# DS157-1_2-C.net
KiCad netlist of a schematic drawn in Altium Designer
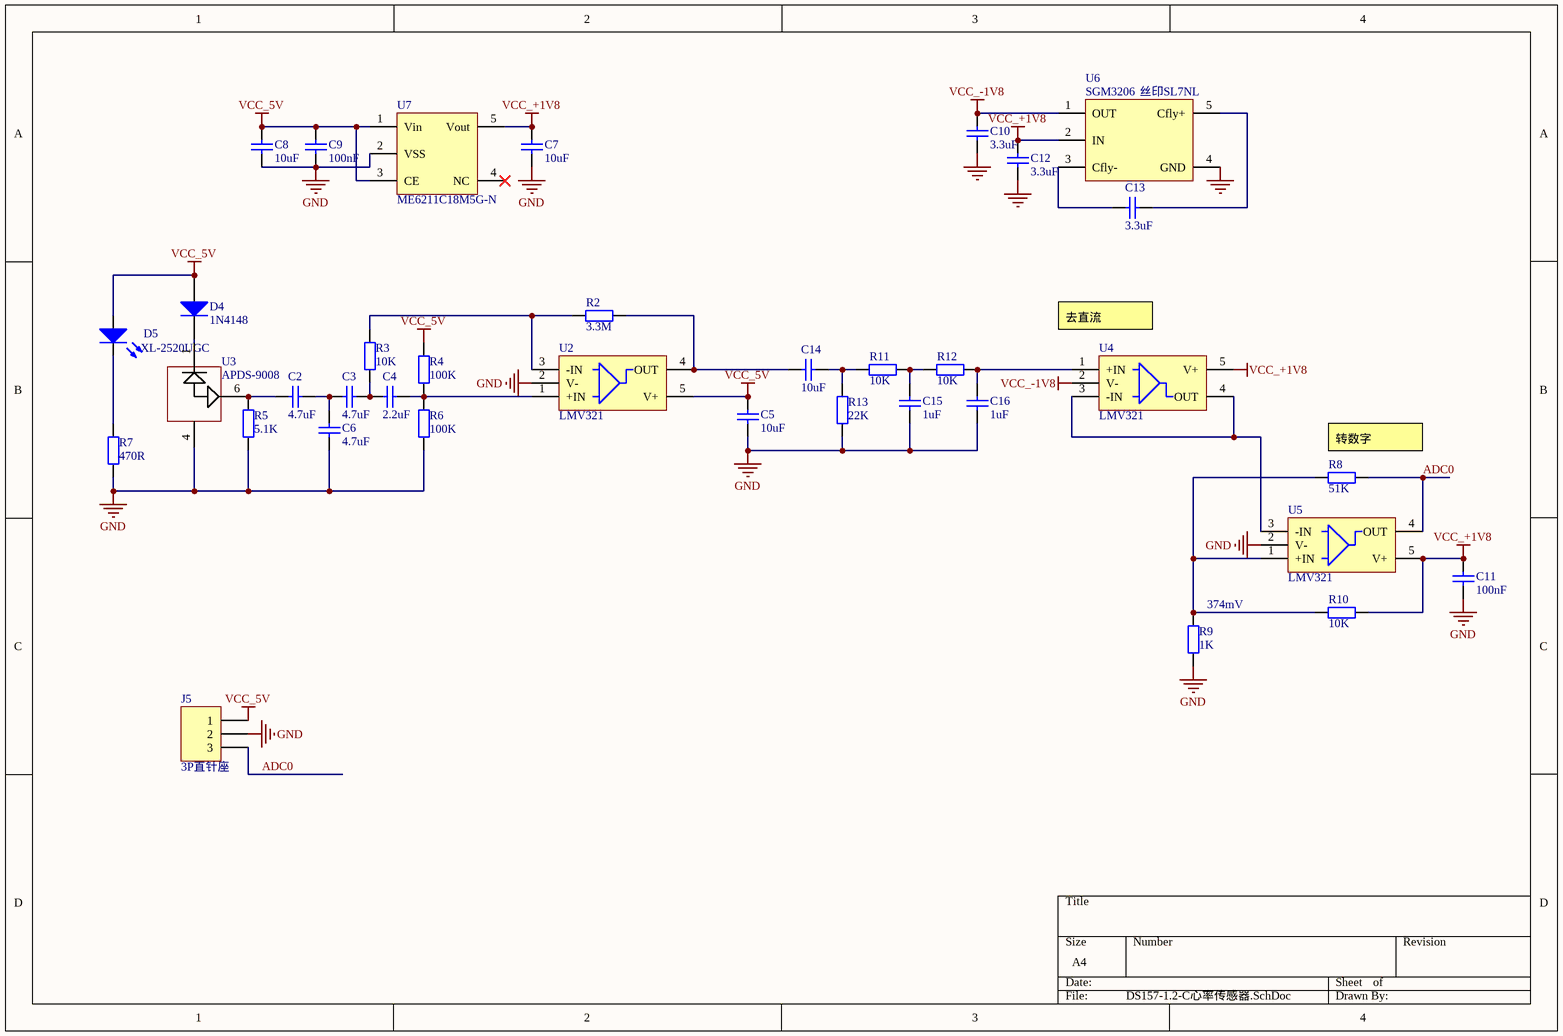
[diagram p0: DS157-1.2-C心率传感器.SchDoc]

(export (version "E")
  (design (tool "Eeschema 10.0.6"))
  (components
    (comp (ref "C2")
      (value "4.7uF")
      (footprint "0603CAP")
      (description "贴片电容")
      (fields (field (name "Comment") "SMDCAP00012"))
      (libsource (lib "AD_SCH") (part "MLCC 4.7uF 50V ±10％ 0603"))
    )
    (comp (ref "C3")
      (value "4.7uF")
      (footprint "0603CAP")
      (description "贴片电容")
      (fields (field (name "Comment") "SMDCAP00012"))
      (libsource (lib "AD_SCH") (part "MLCC 4.7uF 50V ±10％ 0603"))
    )
    (comp (ref "C4")
      (value "2.2uF")
      (footprint "0603CAP")
      (description "贴片电容")
      (fields (field (name "Comment") "MLCC 2.2uF 25V ±10％ 0603"))
      (libsource (lib "AD_SCH") (part "MLCC 2.2uF 25V ±10％ 0603"))
    )
    (comp (ref "C5")
      (value "10uF")
      (footprint "0603CAP")
      (description "贴片电容")
      (fields (field (name "Comment") "SMDCAP00016"))
      (libsource (lib "AD_SCH") (part "MLCC 10uF 50V ±10％ 0603"))
    )
    (comp (ref "C6")
      (value "4.7uF")
      (footprint "0603CAP")
      (description "贴片电容")
      (fields (field (name "Comment") "SMDCAP00012"))
      (libsource (lib "AD_SCH") (part "MLCC 4.7uF 50V ±10％ 0603"))
    )
    (comp (ref "C7")
      (value "10uF")
      (footprint "0603CAP")
      (description "贴片电容")
      (fields (field (name "Comment") "SMDCAP00016"))
      (libsource (lib "AD_SCH") (part "MLCC 10uF 50V ±10％ 0603"))
    )
    (comp (ref "C8")
      (value "10uF")
      (footprint "0603CAP")
      (description "贴片电容")
      (fields (field (name "Comment") "SMDCAP00016"))
      (libsource (lib "AD_SCH") (part "MLCC 10uF 50V ±10％ 0603"))
    )
    (comp (ref "C9")
      (value "100nF")
      (footprint "0603CAP")
      (description "贴片电容")
      (fields (field (name "Comment") "SMDCAP00013"))
      (libsource (lib "AD_SCH") (part "MLCC 100nF 50V ±10％ 0603"))
    )
    (comp (ref "C10")
      (value "3.3uF")
      (footprint "0603CAP")
      (description "贴片电容")
      (fields (field (name "Comment") "MLCC 3.3uF 50V ±10％ 0603"))
      (libsource (lib "AD_SCH") (part "MLCC 3.3uF 50V ±10％ 0603"))
    )
    (comp (ref "C11")
      (value "100nF")
      (footprint "0603CAP")
      (description "贴片电容")
      (fields (field (name "Comment") "SMDCAP00013"))
      (libsource (lib "AD_SCH") (part "MLCC 100nF 50V ±10％ 0603"))
    )
    (comp (ref "C12")
      (value "3.3uF")
      (footprint "0603CAP")
      (description "贴片电容")
      (fields (field (name "Comment") "MLCC 3.3uF 50V ±10％ 0603"))
      (libsource (lib "AD_SCH") (part "MLCC 3.3uF 50V ±10％ 0603"))
    )
    (comp (ref "C13")
      (value "3.3uF")
      (footprint "0603CAP")
      (description "贴片电容")
      (fields (field (name "Comment") "MLCC 3.3uF 50V ±10％ 0603"))
      (libsource (lib "AD_SCH") (part "MLCC 3.3uF 50V ±10％ 0603"))
    )
    (comp (ref "C14")
      (value "10uF")
      (footprint "0603CAP")
      (description "贴片电容")
      (fields (field (name "Comment") "SMDCAP00016"))
      (libsource (lib "AD_SCH") (part "MLCC 10uF 50V ±10％ 0603"))
    )
    (comp (ref "C15")
      (value "1uF")
      (footprint "0603CAP")
      (description "贴片电容")
      (fields (field (name "Comment") "SMDCAP00015"))
      (libsource (lib "AD_SCH") (part "MLCC 1uF 50V ±10％ 0603"))
    )
    (comp (ref "C16")
      (value "1uF")
      (footprint "0603CAP")
      (description "贴片电容")
      (fields (field (name "Comment") "SMDCAP00015"))
      (libsource (lib "AD_SCH") (part "MLCC 1uF 50V ±10％ 0603"))
    )
    (comp (ref "D4")
      (value "1N4148")
      (footprint "SOD-123")
      (description "贴片开关二极管 T4")
      (fields (field (name "Comment") "DIPDIODE02001"))
      (libsource (lib "AD_SCH") (part "1N4148W"))
    )
    (comp (ref "D5")
      (value "XL-2520UGC")
      (footprint "TR10")
      (description "贴片LED")
      (fields (field (name "Comment") "Chip 翠绿LED 0603"))
      (libsource (lib "AD_SCH") (part "Chip LED 0603 翠绿"))
    )
    (comp (ref "J5")
      (value "3P直针座")
      (footprint "XH2.54-3P")
      (fields (field (name "Comment") "SL000000028"))
      (libsource (lib "AD_SCH") (part "XH2.54mm-3A 直针座"))
    )
    (comp (ref "R2")
      (value "3.3M")
      (footprint "0603RES")
      (description "贴片电阻")
      (fields (field (name "Comment") "SMDRES00090"))
      (libsource (lib "AD_SCH") (part "Chip 3.3M 1/16W ±1％ 0603"))
    )
    (comp (ref "R3")
      (value "10K")
      (footprint "0603RES")
      (description "贴片电阻")
      (fields (field (name "Comment") "SMDRES00056"))
      (libsource (lib "") (part "Chip 10K 1/16W ±1％ 0603_1"))
    )
    (comp (ref "R4")
      (value "100K")
      (footprint "0603RES")
      (description "贴片电阻")
      (fields (field (name "Comment") "SMDRES00071"))
      (libsource (lib "AD_SCH") (part "Chip 100K 1/16W ±1％ 0603"))
    )
    (comp (ref "R5")
      (value "5.1K")
      (footprint "0603RES")
      (description "贴片电阻")
      (fields (field (name "Comment") "SMDRES00049"))
      (libsource (lib "AD_SCH") (part "Chip 5.1K 1/16W ±1％ 0603"))
    )
    (comp (ref "R6")
      (value "100K")
      (footprint "0603RES")
      (description "贴片电阻")
      (fields (field (name "Comment") "SMDRES00071"))
      (libsource (lib "AD_SCH") (part "Chip 100K 1/16W ±1％ 0603"))
    )
    (comp (ref "R7")
      (value "470R")
      (footprint "0603RES")
      (description "贴片电阻")
      (fields (field (name "Comment") "SMDRES00027"))
      (libsource (lib "AD_SCH") (part "Chip 470R 1/16W ±1％ 0603"))
    )
    (comp (ref "R8")
      (value "51K")
      (footprint "0603RES")
      (description "贴片电阻")
      (fields (field (name "Comment") "Chip 51K 1/16W ±1％ 0603"))
      (libsource (lib "AD_SCH") (part "Chip 51K 1/16W ±1％ 0603"))
    )
    (comp (ref "R9")
      (value "1K")
      (footprint "0603RES")
      (description "贴片电阻")
      (fields (field (name "Comment") "SMDRES00034"))
      (libsource (lib "AD_SCH") (part "Chip 1K 1/16W ±1％ 0603"))
    )
    (comp (ref "R10")
      (value "10K")
      (footprint "0603RES")
      (description "贴片电阻")
      (fields (field (name "Comment") "SMDRES00056"))
      (libsource (lib "AD_SCH") (part "Chip 10K 1/16W ±1％ 0603"))
    )
    (comp (ref "R11")
      (value "10K")
      (footprint "0603RES")
      (description "贴片电阻")
      (fields (field (name "Comment") "SMDRES00056"))
      (libsource (lib "AD_SCH") (part "Chip 10K 1/16W ±1％ 0603"))
    )
    (comp (ref "R12")
      (value "10K")
      (footprint "0603RES")
      (description "贴片电阻")
      (fields (field (name "Comment") "SMDRES00056"))
      (libsource (lib "AD_SCH") (part "Chip 10K 1/16W ±1％ 0603"))
    )
    (comp (ref "R13")
      (value "22K")
      (footprint "0603RES")
      (description "贴片电阻")
      (fields (field (name "Comment") "SMDRES00108"))
      (libsource (lib "AD_SCH") (part "Chip 22K 1/16W ±1％ 0603"))
    )
    (comp (ref "U2")
      (value "LMV321")
      (footprint "SOT23-5")
      (description "稳压芯片")
      (fields (field (name "Comment") "DIPIC000023"))
      (libsource (lib "") (part "LMV321_1"))
    )
    (comp (ref "U3")
      (value "APDS-9008")
      (footprint "APDS-9008-020")
      (libsource (lib "AD_SCH") (part "APDS-9008"))
    )
    (comp (ref "U4")
      (value "LMV321")
      (footprint "SOT23-5")
      (description "稳压芯片")
      (fields (field (name "Comment") "DIPIC000023"))
      (libsource (lib "AD_SCH") (part "LMV321"))
    )
    (comp (ref "U5")
      (value "LMV321")
      (footprint "SOT23-5")
      (description "稳压芯片")
      (fields (field (name "Comment") "DIPIC000023"))
      (libsource (lib "") (part "LMV321_1"))
    )
    (comp (ref "U6")
      (value "SGM3206")
      (footprint "SOT23-5")
      (description "SGMICRO(圣邦微)\r\nSGM3206YN5G/TR\r\nSOT-23-5")
      (fields (field (name "ALTIUM_VALUE") "丝印SL7NL"))
      (libsource (lib "AD_SCH") (part "SGM3206"))
    )
    (comp (ref "U7")
      (value "ME6211C18M5G-N")
      (footprint "SOT23-5")
      (description "稳压芯片")
      (libsource (lib "AD_SCH") (part "ME6211C18M5G-N"))
    )
  )
  (nets
    (net (code "1") (name "/ADC0") (class "Default")
      (node (ref "J5") (pin "3") (pinfunction "3_3") (pintype "passive"))
      (node (ref "R8") (pin "1") (pinfunction "1_1") (pintype "passive"))
      (node (ref "U5") (pin "4") (pinfunction "OUT_4") (pintype "passive"))
    )
    (net (code "2") (name "GND") (class "Default")
      (node (ref "C10") (pin "2") (pinfunction "2_2") (pintype "passive"))
      (node (ref "C11") (pin "1") (pinfunction "1_1") (pintype "passive"))
      (node (ref "C12") (pin "2") (pinfunction "2_2") (pintype "passive"))
      (node (ref "C15") (pin "1") (pinfunction "1_1") (pintype "passive"))
      (node (ref "C16") (pin "1") (pinfunction "1_1") (pintype "passive"))
      (node (ref "C5") (pin "1") (pinfunction "1_1") (pintype "passive"))
      (node (ref "C6") (pin "1") (pinfunction "1_1") (pintype "passive"))
      (node (ref "C7") (pin "1") (pinfunction "1_1") (pintype "passive"))
      (node (ref "C8") (pin "1") (pinfunction "1_1") (pintype "passive"))
      (node (ref "C9") (pin "1") (pinfunction "1_1") (pintype "passive"))
      (node (ref "J5") (pin "2") (pinfunction "2_2") (pintype "passive"))
      (node (ref "R13") (pin "1") (pinfunction "1_1") (pintype "passive"))
      (node (ref "R5") (pin "1") (pinfunction "1_1") (pintype "passive"))
      (node (ref "R6") (pin "1") (pinfunction "1_1") (pintype "passive"))
      (node (ref "R7") (pin "1") (pinfunction "1_1") (pintype "passive"))
      (node (ref "R9") (pin "1") (pinfunction "1_1") (pintype "passive"))
      (node (ref "U2") (pin "2") (pinfunction "V-_2") (pintype "passive"))
      (node (ref "U3") (pin "4") (pinfunction "gnd_4") (pintype "passive"))
      (node (ref "U5") (pin "2") (pinfunction "V-_2") (pintype "passive"))
      (node (ref "U6") (pin "4") (pinfunction "GND_4") (pintype "passive"))
      (node (ref "U7") (pin "2") (pinfunction "VSS_2") (pintype "passive"))
    )
    (net (code "3") (name "Net-(C2-Pad2)") (class "Default")
      (node (ref "C2") (pin "2") (pinfunction "2_2") (pintype "passive"))
      (node (ref "C3") (pin "1") (pinfunction "1_1") (pintype "passive"))
      (node (ref "C6") (pin "2") (pinfunction "2_2") (pintype "passive"))
    )
    (net (code "4") (name "Net-(C3-Pad2)") (class "Default")
      (node (ref "C3") (pin "2") (pinfunction "2_2") (pintype "passive"))
      (node (ref "C4") (pin "1") (pinfunction "1_1") (pintype "passive"))
      (node (ref "R3") (pin "1") (pinfunction "1_1") (pintype "passive"))
    )
    (net (code "5") (name "Net-(C14-Pad1)") (class "Default")
      (node (ref "C14") (pin "1") (pinfunction "1_1") (pintype "passive"))
      (node (ref "R11") (pin "1") (pinfunction "1_1") (pintype "passive"))
      (node (ref "R13") (pin "2") (pinfunction "2_2") (pintype "passive"))
    )
    (net (code "6") (name "Net-(C15-Pad2)") (class "Default")
      (node (ref "C15") (pin "2") (pinfunction "2_2") (pintype "passive"))
      (node (ref "R11") (pin "2") (pinfunction "2_2") (pintype "passive"))
      (node (ref "R12") (pin "1") (pinfunction "1_1") (pintype "passive"))
    )
    (net (code "7") (name "Net-(D4-K)") (class "Default")
      (node (ref "D4") (pin "2") (pinfunction "K_2") (pintype "passive"))
      (node (ref "U3") (pin "1") (pinfunction "VCC_1") (pintype "passive"))
    )
    (net (code "8") (name "Net-(D5-K)") (class "Default")
      (node (ref "D5") (pin "2") (pinfunction "K_2") (pintype "passive"))
      (node (ref "R7") (pin "2") (pinfunction "2_2") (pintype "passive"))
    )
    (net (code "9") (name "Net-(U2-+IN)") (class "Default")
      (node (ref "C4") (pin "2") (pinfunction "2_2") (pintype "passive"))
      (node (ref "R4") (pin "1") (pinfunction "1_1") (pintype "passive"))
      (node (ref "R6") (pin "2") (pinfunction "2_2") (pintype "passive"))
      (node (ref "U2") (pin "1") (pinfunction "+IN_1") (pintype "passive"))
    )
    (net (code "10") (name "Net-(U2--IN)") (class "Default")
      (node (ref "R2") (pin "1") (pinfunction "1_1") (pintype "passive"))
      (node (ref "R3") (pin "2") (pinfunction "2_2") (pintype "passive"))
      (node (ref "U2") (pin "3") (pinfunction "-IN_3") (pintype "passive"))
    )
    (net (code "11") (name "Net-(U2-OUT)") (class "Default")
      (node (ref "C14") (pin "2") (pinfunction "2_2") (pintype "passive"))
      (node (ref "R2") (pin "2") (pinfunction "2_2") (pintype "passive"))
      (node (ref "U2") (pin "4") (pinfunction "OUT_4") (pintype "passive"))
    )
    (net (code "12") (name "Net-(U3-out)") (class "Default")
      (node (ref "C2") (pin "1") (pinfunction "1_1") (pintype "passive"))
      (node (ref "R5") (pin "2") (pinfunction "2_2") (pintype "passive"))
      (node (ref "U3") (pin "6") (pinfunction "out_6") (pintype "passive"))
    )
    (net (code "13") (name "Net-(U4-+IN)") (class "Default")
      (node (ref "C16") (pin "2") (pinfunction "2_2") (pintype "passive"))
      (node (ref "R12") (pin "2") (pinfunction "2_2") (pintype "passive"))
      (node (ref "U4") (pin "1") (pinfunction "+IN_1") (pintype "passive"))
    )
    (net (code "14") (name "Net-(U4--IN)") (class "Default")
      (node (ref "U4") (pin "3") (pinfunction "-IN_3") (pintype "passive"))
      (node (ref "U4") (pin "4") (pinfunction "OUT_4") (pintype "passive"))
      (node (ref "U5") (pin "3") (pinfunction "-IN_3") (pintype "passive"))
    )
    (net (code "15") (name "Net-(U5-+IN)") (class "Default")
      (node (ref "R10") (pin "1") (pinfunction "1_1") (pintype "passive"))
      (node (ref "R8") (pin "2") (pinfunction "2_2") (pintype "passive"))
      (node (ref "R9") (pin "2") (pinfunction "2_2") (pintype "passive"))
      (node (ref "U5") (pin "1") (pinfunction "+IN_1") (pintype "passive"))
    )
    (net (code "16") (name "Net-(U6-Cfly+)") (class "Default")
      (node (ref "C13") (pin "2") (pinfunction "2_2") (pintype "passive"))
      (node (ref "U6") (pin "5") (pinfunction "Cfly+_5") (pintype "passive"))
    )
    (net (code "17") (name "Net-(U6-Cfly-)") (class "Default")
      (node (ref "C13") (pin "1") (pinfunction "1_1") (pintype "passive"))
      (node (ref "U6") (pin "3") (pinfunction "Cfly-_3") (pintype "passive"))
    )
    (net (code "18") (name "VCC_+1V8") (class "Default")
      (node (ref "C11") (pin "2") (pinfunction "2_2") (pintype "passive"))
      (node (ref "C12") (pin "1") (pinfunction "1_1") (pintype "passive"))
      (node (ref "C7") (pin "2") (pinfunction "2_2") (pintype "passive"))
      (node (ref "R10") (pin "2") (pinfunction "2_2") (pintype "passive"))
      (node (ref "U4") (pin "5") (pinfunction "V+_5") (pintype "passive"))
      (node (ref "U5") (pin "5") (pinfunction "V+_5") (pintype "passive"))
      (node (ref "U6") (pin "2") (pinfunction "IN_2") (pintype "passive"))
      (node (ref "U7") (pin "5") (pinfunction "Vout_5") (pintype "passive"))
    )
    (net (code "19") (name "VCC_-1V8") (class "Default")
      (node (ref "C10") (pin "1") (pinfunction "1_1") (pintype "passive"))
      (node (ref "U4") (pin "2") (pinfunction "V-_2") (pintype "passive"))
      (node (ref "U6") (pin "1") (pinfunction "OUT_1") (pintype "passive"))
    )
    (net (code "20") (name "VCC_5V") (class "Default")
      (node (ref "C5") (pin "2") (pinfunction "2_2") (pintype "passive"))
      (node (ref "C8") (pin "2") (pinfunction "2_2") (pintype "passive"))
      (node (ref "C9") (pin "2") (pinfunction "2_2") (pintype "passive"))
      (node (ref "D4") (pin "1") (pinfunction "A_1") (pintype "passive"))
      (node (ref "D5") (pin "1") (pinfunction "A_1") (pintype "passive"))
      (node (ref "J5") (pin "1") (pinfunction "1_1") (pintype "passive"))
      (node (ref "R4") (pin "2") (pinfunction "2_2") (pintype "passive"))
      (node (ref "U2") (pin "5") (pinfunction "V+_5") (pintype "passive"))
      (node (ref "U7") (pin "1") (pinfunction "Vin_1") (pintype "passive"))
      (node (ref "U7") (pin "3") (pinfunction "CE_3") (pintype "passive"))
    )
    (net (code "21") (name "unconnected-(U7-NC-Pad4)") (class "Default")
      (node (ref "U7") (pin "4") (pinfunction "NC_4") (pintype "passive+no_connect"))
    )
  )
)
